# Kompass_ControlFramePTH.net
KiCad netlist of a schematic drawn in EAGLE
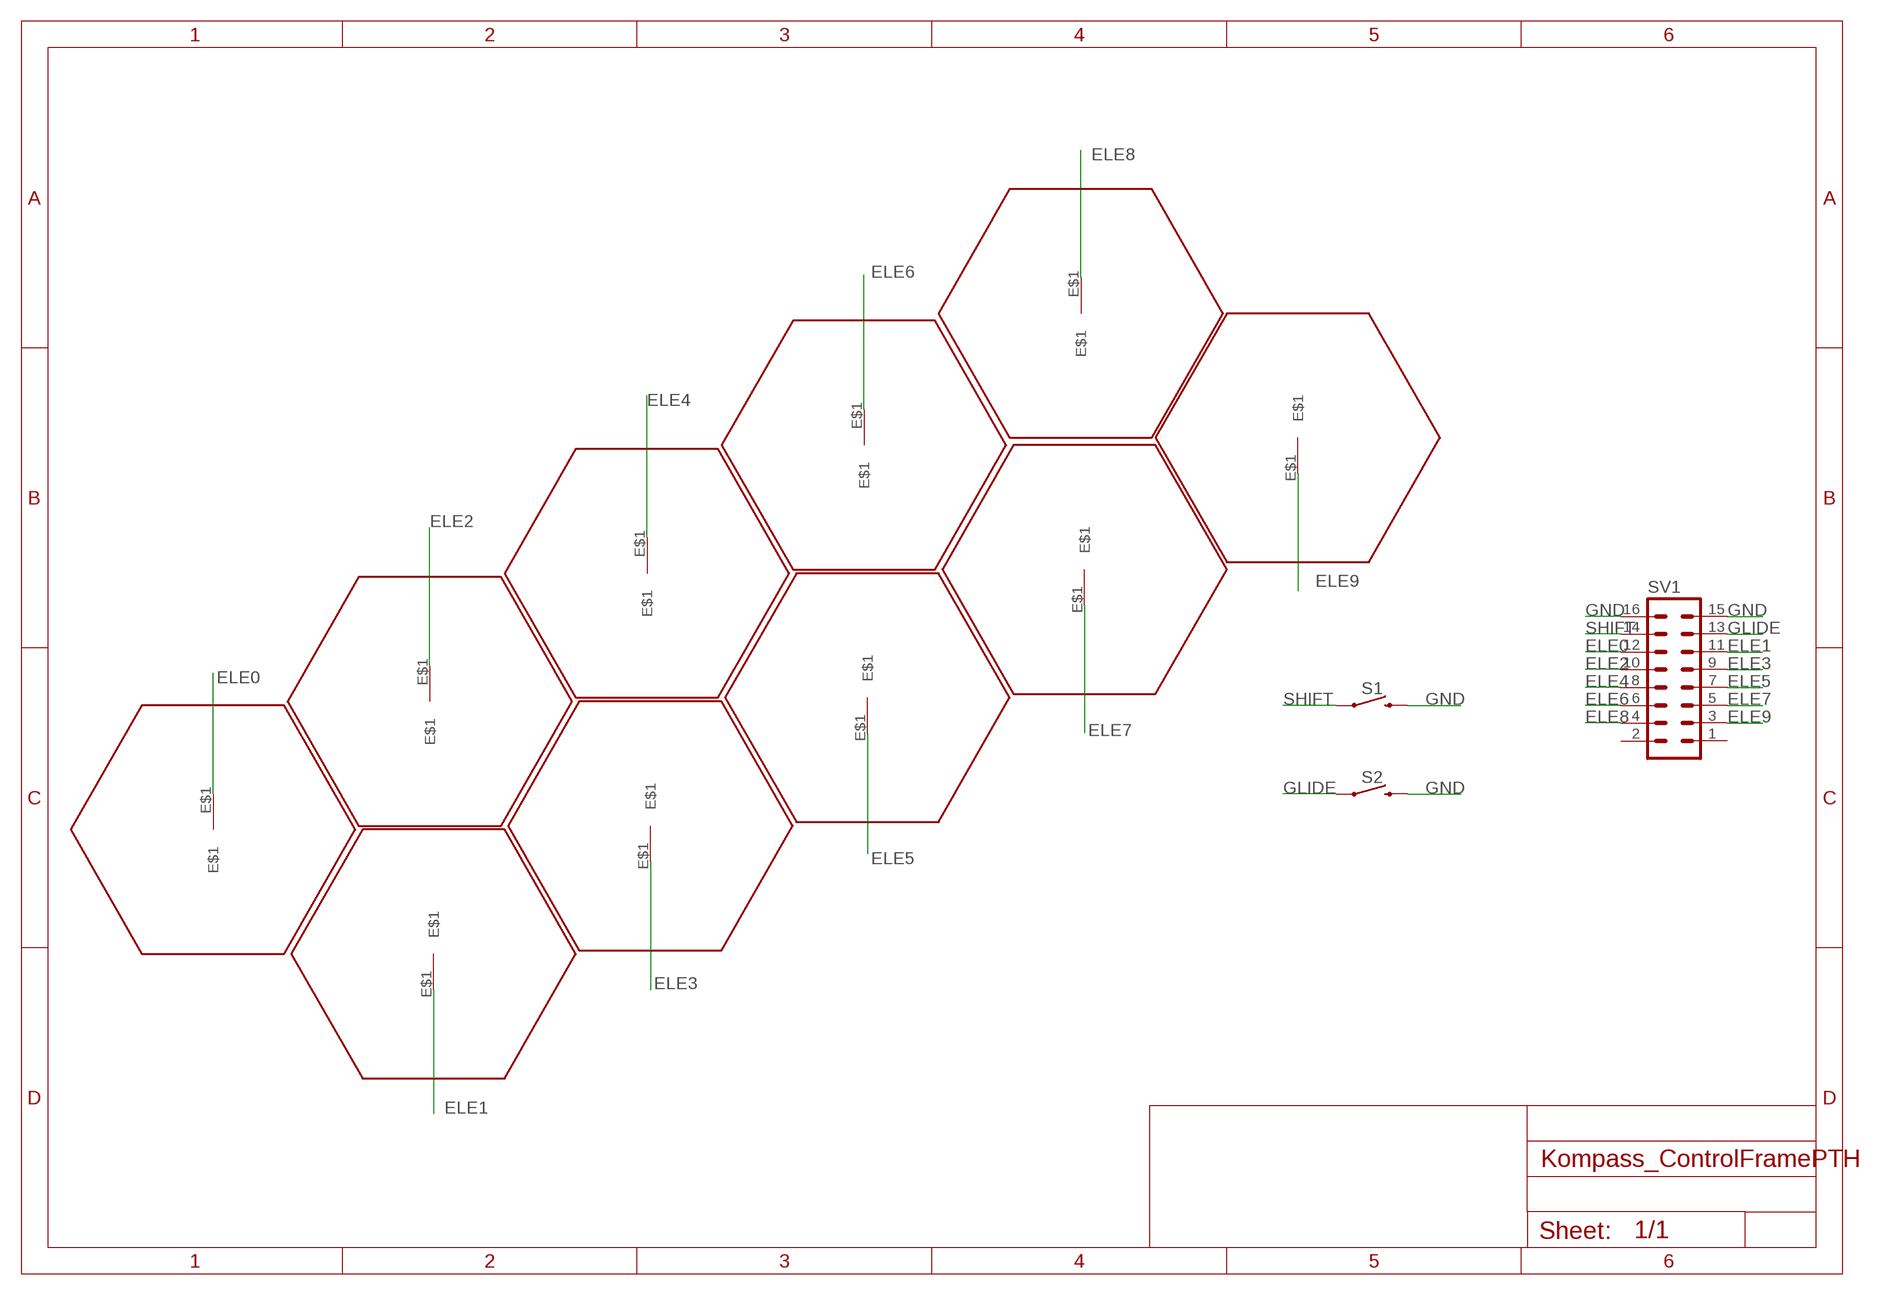
[diagram p0: schematic, sheet 1]

(export (version "E")
  (design (tool "Eeschema 10.0.6"))
  (components
    (comp (ref "ELE0")
      (value "HEX_ELECTRODEHEX_ELECTRODEPAD")
      (footprint "eagle-import:HEX_ELECTRODE")
      (libsource (lib "eagle-import") (part "HEX_ELECTRODEHEX_ELECTRODEPAD"))
    )
    (comp (ref "ELE1")
      (value "HEX_ELECTRODEHEX_ELECTRODEPAD")
      (footprint "eagle-import:HEX_ELECTRODE")
      (libsource (lib "eagle-import") (part "HEX_ELECTRODEHEX_ELECTRODEPAD"))
    )
    (comp (ref "ELE2")
      (value "HEX_ELECTRODEHEX_ELECTRODEPAD")
      (footprint "eagle-import:HEX_ELECTRODE")
      (libsource (lib "eagle-import") (part "HEX_ELECTRODEHEX_ELECTRODEPAD"))
    )
    (comp (ref "ELE3")
      (value "HEX_ELECTRODEHEX_ELECTRODEPAD")
      (footprint "eagle-import:HEX_ELECTRODE")
      (libsource (lib "eagle-import") (part "HEX_ELECTRODEHEX_ELECTRODEPAD"))
    )
    (comp (ref "ELE4")
      (value "HEX_ELECTRODEHEX_ELECTRODEPAD")
      (footprint "eagle-import:HEX_ELECTRODE")
      (libsource (lib "eagle-import") (part "HEX_ELECTRODEHEX_ELECTRODEPAD"))
    )
    (comp (ref "ELE5")
      (value "HEX_ELECTRODEHEX_ELECTRODEPAD")
      (footprint "eagle-import:HEX_ELECTRODE")
      (libsource (lib "eagle-import") (part "HEX_ELECTRODEHEX_ELECTRODEPAD"))
    )
    (comp (ref "ELE6")
      (value "HEX_ELECTRODEHEX_ELECTRODEPAD")
      (footprint "eagle-import:HEX_ELECTRODE")
      (libsource (lib "eagle-import") (part "HEX_ELECTRODEHEX_ELECTRODEPAD"))
    )
    (comp (ref "ELE7")
      (value "HEX_ELECTRODEHEX_ELECTRODEPAD")
      (footprint "eagle-import:HEX_ELECTRODE")
      (libsource (lib "eagle-import") (part "HEX_ELECTRODEHEX_ELECTRODEPAD"))
    )
    (comp (ref "ELE8")
      (value "HEX_ELECTRODEHEX_ELECTRODEPAD")
      (footprint "eagle-import:HEX_ELECTRODE")
      (libsource (lib "eagle-import") (part "HEX_ELECTRODEHEX_ELECTRODEPAD"))
    )
    (comp (ref "ELE9")
      (value "HEX_ELECTRODEHEX_ELECTRODEPAD")
      (footprint "eagle-import:HEX_ELECTRODE")
      (libsource (lib "eagle-import") (part "HEX_ELECTRODEHEX_ELECTRODEPAD"))
    )
    (comp (ref "S1")
      (value "MOMENTARY-SWITCH-SPST-PTH-6.0MM-KIT")
      (footprint "eagle-import:TACTILE_SWITCH_PTH_6.0MM_KIT")
      (libsource (lib "eagle-import") (part "MOMENTARY-SWITCH-SPST-PTH-6.0MM-KIT"))
    )
    (comp (ref "S2")
      (value "MOMENTARY-SWITCH-SPST-PTH-6.0MM-KIT")
      (footprint "eagle-import:TACTILE_SWITCH_PTH_6.0MM_KIT")
      (libsource (lib "eagle-import") (part "MOMENTARY-SWITCH-SPST-PTH-6.0MM-KIT"))
    )
    (comp (ref "SV1")
      (value "MA08-2")
      (footprint "eagle-import:MA08-2")
      (libsource (lib "eagle-import") (part "MA08-2"))
    )
  )
  (nets
    (net (code "1") (name "/ELE0") (class "Default")
      (node (ref "ELE0") (pin "E$1") (pinfunction "E$1_E$1") (pintype "bidirectional"))
      (node (ref "SV1") (pin "12") (pinfunction "12_12") (pintype "passive"))
    )
    (net (code "2") (name "/ELE1") (class "Default")
      (node (ref "ELE1") (pin "E$1") (pinfunction "E$1_E$1") (pintype "bidirectional"))
      (node (ref "SV1") (pin "11") (pinfunction "11_11") (pintype "passive"))
    )
    (net (code "3") (name "/ELE2") (class "Default")
      (node (ref "ELE2") (pin "E$1") (pinfunction "E$1_E$1") (pintype "bidirectional"))
      (node (ref "SV1") (pin "10") (pinfunction "10_10") (pintype "passive"))
    )
    (net (code "4") (name "/ELE3") (class "Default")
      (node (ref "ELE3") (pin "E$1") (pinfunction "E$1_E$1") (pintype "bidirectional"))
      (node (ref "SV1") (pin "9") (pinfunction "9_9") (pintype "passive"))
    )
    (net (code "5") (name "/ELE4") (class "Default")
      (node (ref "ELE4") (pin "E$1") (pinfunction "E$1_E$1") (pintype "bidirectional"))
      (node (ref "SV1") (pin "8") (pinfunction "8_8") (pintype "passive"))
    )
    (net (code "6") (name "/ELE5") (class "Default")
      (node (ref "ELE5") (pin "E$1") (pinfunction "E$1_E$1") (pintype "bidirectional"))
      (node (ref "SV1") (pin "7") (pinfunction "7_7") (pintype "passive"))
    )
    (net (code "7") (name "/ELE6") (class "Default")
      (node (ref "ELE6") (pin "E$1") (pinfunction "E$1_E$1") (pintype "bidirectional"))
      (node (ref "SV1") (pin "6") (pinfunction "6_6") (pintype "passive"))
    )
    (net (code "8") (name "/ELE7") (class "Default")
      (node (ref "ELE7") (pin "E$1") (pinfunction "E$1_E$1") (pintype "bidirectional"))
      (node (ref "SV1") (pin "5") (pinfunction "5_5") (pintype "passive"))
    )
    (net (code "9") (name "/ELE8") (class "Default")
      (node (ref "ELE8") (pin "E$1") (pinfunction "E$1_E$1") (pintype "bidirectional"))
      (node (ref "SV1") (pin "4") (pinfunction "4_4") (pintype "passive"))
    )
    (net (code "10") (name "/ELE9") (class "Default")
      (node (ref "ELE9") (pin "E$1") (pinfunction "E$1_E$1") (pintype "bidirectional"))
      (node (ref "SV1") (pin "3") (pinfunction "3_3") (pintype "passive"))
    )
    (net (code "11") (name "/GLIDE") (class "Default")
      (node (ref "S2") (pin "1") (pinfunction "1_1") (pintype "passive"))
      (node (ref "SV1") (pin "13") (pinfunction "13_13") (pintype "passive"))
    )
    (net (code "12") (name "/GND") (class "Default")
      (node (ref "S1") (pin "3") (pinfunction "2_3") (pintype "passive"))
      (node (ref "S2") (pin "3") (pinfunction "2_3") (pintype "passive"))
      (node (ref "SV1") (pin "15") (pinfunction "15_15") (pintype "passive"))
      (node (ref "SV1") (pin "16") (pinfunction "16_16") (pintype "passive"))
    )
    (net (code "13") (name "/SHIFT") (class "Default")
      (node (ref "S1") (pin "1") (pinfunction "1_1") (pintype "passive"))
      (node (ref "SV1") (pin "14") (pinfunction "14_14") (pintype "passive"))
    )
    (net (code "14") (name "unconnected-(SV1-Pad1)") (class "Default")
      (node (ref "SV1") (pin "1") (pinfunction "1_1") (pintype "passive"))
    )
    (net (code "15") (name "unconnected-(SV1-Pad2)") (class "Default")
      (node (ref "SV1") (pin "2") (pinfunction "2_2") (pintype "passive"))
    )
  )
)
